# US_SB_USB.net
KiCad netlist of a schematic drawn in Altium Designer
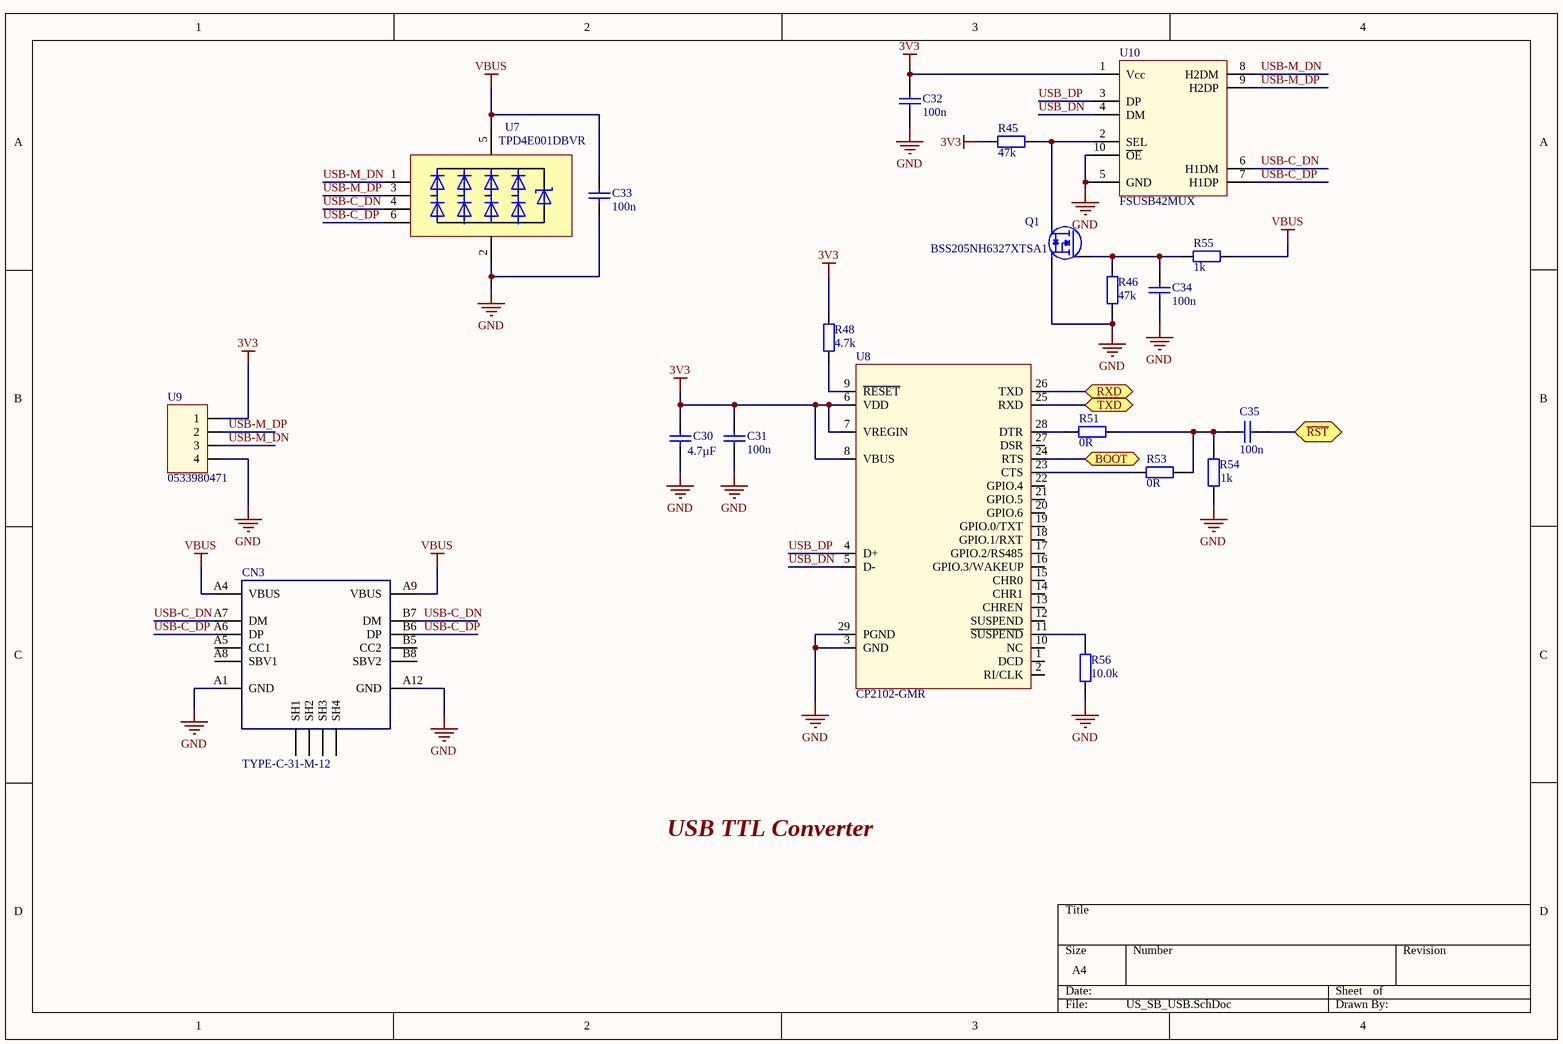
[diagram p0: US_SB_USB.SchDoc]

(export (version "E")
  (design (tool "Eeschema 10.0.6"))
  (components
    (comp (ref "C30")
      (value "4.7µF")
      (footprint "C0603_IPC_HD")
      (description "4.7µF ±10% 10V Ceramic Capacitor X5R 0603 (1608 Metric)")
      (fields
        (field (name "MANUFACTURER") "Samsung Electro-Mechanics")
        (field (name "MANUFACTURER PART NUMBER") "CL10A475KP8NNNC")
      )
      (libsource (lib "alfasat_lib_eps") (part "CL0603_4.7uF_10V"))
    )
    (comp (ref "C31")
      (value "100n")
      (footprint "C0603_IPC_HD")
      (description "CAP CER 0.1UF 16V X7R 0603")
      (fields
        (field (name "MANUFACTURER") "Samsung Electro-Mechanics")
        (field (name "MANUFACTURER PART NUMBER") "CL10B104KO8NNNC")
      )
      (libsource (lib "alfasat_parts_lib") (part "CL10B104KO8NNNC"))
    )
    (comp (ref "C32")
      (value "100n")
      (footprint "C0603_IPC_HD")
      (description "CAP CER 0.1UF 16V X7R 0603")
      (fields
        (field (name "MANUFACTURER") "Samsung Electro-Mechanics")
        (field (name "MANUFACTURER PART NUMBER") "CL10B104KO8NNNC")
      )
      (libsource (lib "alfasat_parts_lib") (part "CL10B104KO8NNNC"))
    )
    (comp (ref "C33")
      (value "100n")
      (footprint "C0603_IPC_HD")
      (description "CAP CER 0.1UF 16V X7R 0603")
      (fields
        (field (name "MANUFACTURER") "Samsung Electro-Mechanics")
        (field (name "MANUFACTURER PART NUMBER") "CL10B104KO8NNNC")
      )
      (libsource (lib "alfasat_parts_lib") (part "CL10B104KO8NNNC"))
    )
    (comp (ref "C34")
      (value "100n")
      (footprint "C0603_IPC_HD")
      (description "CAP CER 0.1UF 16V X7R 0603")
      (fields
        (field (name "MANUFACTURER") "Samsung Electro-Mechanics")
        (field (name "MANUFACTURER PART NUMBER") "CL10B104KO8NNNC")
      )
      (libsource (lib "alfasat_parts_lib") (part "CL10B104KO8NNNC"))
    )
    (comp (ref "C35")
      (value "100n")
      (footprint "C0603_IPC_HD")
      (description "CAP CER 0.1UF 16V X7R 0603")
      (fields
        (field (name "MANUFACTURER") "Samsung Electro-Mechanics")
        (field (name "MANUFACTURER PART NUMBER") "CL10B104KO8NNNC")
      )
      (libsource (lib "alfasat_parts_lib") (part "CL10B104KO8NNNC"))
    )
    (comp (ref "CN3")
      (value "TYPE-C-31-M-12")
      (footprint "TYPE-C-C165948")
      (description "TYPE C PCB TH CONN")
      (fields (field (name "MANUFACTURER") "Korean Hroparts Elec"))
      (libsource (lib "alfasat_lib") (part "TYPE-C-31-M-12"))
    )
    (comp (ref "Q1")
      (value "BSS205NH6327XTSA1")
      (description "N-Channel 20V 2.5A (Ta) 500mW (Ta) Surface Mount SOT-23-3")
      (fields (field (name "MANUFACTURER") "Infineon Technologies"))
      (libsource (lib "alfasat_lib_eps") (part "BSS205NH6327XTSA1"))
    )
    (comp (ref "R45")
      (value "47k")
      (footprint "R0603_IPC_HD")
      (description "RES SMD 47K OHM 5% 1/10W 0603")
      (fields
        (field (name "MANUFACTURER") "Bourns Inc.")
        (field (name "MANUFACTURER PART NUMBER") "CR0603-JW-473ELF")
      )
      (libsource (lib "") (part "CR0603-JW-473ELF_1"))
    )
    (comp (ref "R46")
      (value "47k")
      (footprint "R0603_IPC_HD")
      (description "RES SMD 47K OHM 5% 1/10W 0603")
      (fields
        (field (name "MANUFACTURER") "Bourns Inc.")
        (field (name "MANUFACTURER PART NUMBER") "CR0603-JW-473ELF")
      )
      (libsource (lib "alfasat_lib_eps") (part "CR0603-JW-473ELF"))
    )
    (comp (ref "R48")
      (value "4.7k")
      (footprint "R0603_IPC_HD")
      (description "RES SMD 4.7K OHM 5% 1/10W 0603")
      (fields
        (field (name "MANUFACTURER") "Bourns Inc.")
        (field (name "MANUFACTURER PART NUMBER") "CR0603-JW-472ELF")
      )
      (libsource (lib "alfasat_lib_eps") (part "CR0603-JW-4.7k"))
    )
    (comp (ref "R51")
      (value "0R")
      (footprint "R0603_IPC_MD")
      (description "RES SMD 0 OHM JUMPER 1/10W 0603")
      (fields
        (field (name "MANUFACTURER") "Bourns Inc.")
        (field (name "MANUFACTURER PART NUMBER") "CR0603-J/-000ELF")
      )
      (libsource (lib "alfasat_lib") (part "CR0603-J/-000ELF"))
    )
    (comp (ref "R53")
      (value "0R")
      (footprint "R0603_IPC_MD")
      (description "RES SMD 0 OHM JUMPER 1/10W 0603")
      (fields
        (field (name "MANUFACTURER") "Bourns Inc.")
        (field (name "MANUFACTURER PART NUMBER") "CR0603-J/-000ELF")
      )
      (libsource (lib "alfasat_lib") (part "CR0603-J/-000ELF"))
    )
    (comp (ref "R54")
      (value "1k")
      (footprint "R0603_IPC_MD")
      (description "RES SMD 1K OHM 5% 1/10W 0603")
      (fields
        (field (name "MANUFACTURER") "Bourns Inc.")
        (field (name "MANUFACTURER PART NUMBER") "CR0603-JW-102ELF")
      )
      (libsource (lib "alfasat_lib") (part "CR0603-JW-102ELF"))
    )
    (comp (ref "R55")
      (value "1k")
      (footprint "R0603_IPC_MD")
      (description "RES SMD 1K OHM 5% 1/10W 0603")
      (fields
        (field (name "MANUFACTURER") "Bourns Inc.")
        (field (name "MANUFACTURER PART NUMBER") "CR0603-JW-102ELF")
      )
      (libsource (lib "") (part "CR0603-JW-102ELF_1"))
    )
    (comp (ref "R56")
      (value "10.0k")
      (footprint "R0603_IPC_MD")
      (description "RES 10K OHM 1% 1/10W 0603")
      (fields
        (field (name "MANUFACTURER") "Stackpole Electronics Inc")
        (field (name "MANUFACTURER PART NUMBER") "RMCF0603FT10K0")
      )
      (libsource (lib "alfasat_parts_lib") (part "RMCF0603FT10K0"))
    )
    (comp (ref "U7")
      (value "TPD4E001DBVR")
      (footprint "SOT23-6")
      (description "4x TVS DIODE 5.5V SOT23-6")
      (fields (field (name "MANUFACTURER") "TI"))
      (libsource (lib "alfasat_parts_lib") (part "TPD4E001DBVR"))
    )
    (comp (ref "U8")
      (value "CP2102-GMR")
      (footprint "CP2102\\9_QFN50P500X500X80_HS-29N")
      (description "USB Bridge, USB to UART USB 2.0 UART Interface 28-QFN (5x5)")
      (fields
        (field (name "MANUFACTURER") "Silicon Labs")
        (field (name "MANUFACTURER PART NUMBER") "CP2102N-A01-GQFN28R")
      )
      (libsource (lib "alfasat_lib_eps") (part "CP2102N-A01-GQFN28R"))
    )
    (comp (ref "U9")
      (value "0533980471")
      (footprint "PB_53261-0471_Right")
      (description "Connector Header Surface Mount 4 position 0.049\" (1.25mm)")
      (fields (field (name "MANUFACTURER") "Molex"))
      (libsource (lib "alfasat_lib_eps") (part "PB_053398_0471"))
    )
    (comp (ref "U10")
      (value "FSUSB42MUX")
      (footprint "MSOP-10")
      (description "IC USB SWITCH DPDT 10MSOP")
      (fields (field (name "MANUFACTURER") "ON Semiconductor"))
      (libsource (lib "alfasat_lib") (part "FSUSB42MUX"))
    )
  )
  (nets
    (net (code "1") (name "/BOOT") (class "Default")
      (node (ref "U8") (pin "24") (pinfunction "RTS_24") (pintype "passive"))
    )
    (net (code "2") (name "/RXD") (class "Default")
      (node (ref "U8") (pin "26") (pinfunction "TXD_26") (pintype "passive"))
    )
    (net (code "3") (name "/TXD") (class "Default")
      (node (ref "U8") (pin "25") (pinfunction "RXD_25") (pintype "passive"))
    )
    (net (code "4") (name "/USB-C_DN") (class "Default")
      (node (ref "CN3") (pin "A7") (pinfunction "DM_A7") (pintype "passive"))
      (node (ref "CN3") (pin "B7") (pinfunction "DM_B7") (pintype "passive"))
      (node (ref "U10") (pin "6") (pinfunction "H1DM_6") (pintype "passive"))
      (node (ref "U7") (pin "4") (pinfunction "IO3_4") (pintype "passive"))
    )
    (net (code "5") (name "/USB-C_DP") (class "Default")
      (node (ref "CN3") (pin "A6") (pinfunction "DP_A6") (pintype "passive"))
      (node (ref "CN3") (pin "B6") (pinfunction "DP_B6") (pintype "passive"))
      (node (ref "U10") (pin "7") (pinfunction "H1DP_7") (pintype "passive"))
      (node (ref "U7") (pin "6") (pinfunction "IO4_6") (pintype "passive"))
    )
    (net (code "6") (name "/USB-M_DN") (class "Default")
      (node (ref "U10") (pin "8") (pinfunction "H2DM_8") (pintype "passive"))
      (node (ref "U7") (pin "1") (pinfunction "IO1_1") (pintype "passive"))
      (node (ref "U9") (pin "3") (pinfunction "3_3") (pintype "passive"))
    )
    (net (code "7") (name "/USB-M_DP") (class "Default")
      (node (ref "U10") (pin "9") (pinfunction "H2DP_9") (pintype "passive"))
      (node (ref "U7") (pin "3") (pinfunction "IO2_3") (pintype "passive"))
      (node (ref "U9") (pin "2") (pinfunction "2_2") (pintype "passive"))
    )
    (net (code "8") (name "/USB_DN") (class "Default")
      (node (ref "U10") (pin "4") (pinfunction "DM_4") (pintype "passive"))
      (node (ref "U8") (pin "5") (pinfunction "D-_5") (pintype "passive"))
    )
    (net (code "9") (name "/USB_DP") (class "Default")
      (node (ref "U10") (pin "3") (pinfunction "DP_3") (pintype "passive"))
      (node (ref "U8") (pin "4") (pinfunction "D+_4") (pintype "passive"))
    )
    (net (code "10") (name "/~{RST}") (class "Default")
      (node (ref "C35") (pin "1") (pinfunction "1_1") (pintype "passive"))
    )
    (net (code "11") (name "3V3") (class "Default")
      (node (ref "C30") (pin "2") (pinfunction "2_2") (pintype "passive"))
      (node (ref "C31") (pin "2") (pinfunction "2_2") (pintype "passive"))
      (node (ref "C32") (pin "2") (pinfunction "2_2") (pintype "passive"))
      (node (ref "R45") (pin "2") (pinfunction "2_2") (pintype "passive"))
      (node (ref "R48") (pin "2") (pinfunction "2_2") (pintype "passive"))
      (node (ref "U10") (pin "1") (pinfunction "Vcc_1") (pintype "passive"))
      (node (ref "U8") (pin "6") (pinfunction "VDD_6") (pintype "passive"))
      (node (ref "U8") (pin "7") (pinfunction "VREGIN_7") (pintype "passive"))
      (node (ref "U8") (pin "8") (pinfunction "VBUS_8") (pintype "passive"))
      (node (ref "U9") (pin "1") (pinfunction "1_1") (pintype "passive"))
    )
    (net (code "12") (name "GND") (class "Default")
      (node (ref "C30") (pin "1") (pinfunction "1_1") (pintype "passive"))
      (node (ref "C31") (pin "1") (pinfunction "1_1") (pintype "passive"))
      (node (ref "C32") (pin "1") (pinfunction "1_1") (pintype "passive"))
      (node (ref "C33") (pin "1") (pinfunction "1_1") (pintype "passive"))
      (node (ref "C34") (pin "1") (pinfunction "1_1") (pintype "passive"))
      (node (ref "CN3") (pin "A1") (pinfunction "GND_A1") (pintype "passive"))
      (node (ref "CN3") (pin "A12") (pinfunction "GND_A12") (pintype "passive"))
      (node (ref "Q1") (pin "2") (pinfunction "S_2") (pintype "passive"))
      (node (ref "R46") (pin "2") (pinfunction "2_2") (pintype "passive"))
      (node (ref "R54") (pin "1") (pinfunction "1_1") (pintype "passive"))
      (node (ref "R56") (pin "1") (pinfunction "1_1") (pintype "passive"))
      (node (ref "U10") (pin "10") (pinfunction "~{OE}_10") (pintype "passive"))
      (node (ref "U10") (pin "5") (pinfunction "GND_5") (pintype "passive"))
      (node (ref "U7") (pin "2") (pinfunction "GND_2") (pintype "power_in"))
      (node (ref "U8") (pin "29") (pinfunction "PGND_29") (pintype "passive"))
      (node (ref "U8") (pin "3") (pinfunction "GND_3") (pintype "passive"))
      (node (ref "U9") (pin "4") (pinfunction "4_4") (pintype "passive"))
    )
    (net (code "13") (name "Net-(C35-Pad2)") (class "Default")
      (node (ref "C35") (pin "2") (pinfunction "2_2") (pintype "passive"))
      (node (ref "R51") (pin "1") (pinfunction "1_1") (pintype "passive"))
      (node (ref "R53") (pin "1") (pinfunction "1_1") (pintype "passive"))
      (node (ref "R54") (pin "2") (pinfunction "2_2") (pintype "passive"))
    )
    (net (code "14") (name "Net-(Q1-D)") (class "Default")
      (node (ref "Q1") (pin "3") (pinfunction "D_3") (pintype "passive"))
      (node (ref "R45") (pin "1") (pinfunction "1_1") (pintype "passive"))
      (node (ref "U10") (pin "2") (pinfunction "SEL_2") (pintype "passive"))
    )
    (net (code "15") (name "Net-(Q1-G)") (class "Default")
      (node (ref "C34") (pin "2") (pinfunction "2_2") (pintype "passive"))
      (node (ref "Q1") (pin "1") (pinfunction "G_1") (pintype "passive"))
      (node (ref "R46") (pin "1") (pinfunction "1_1") (pintype "passive"))
      (node (ref "R55") (pin "2") (pinfunction "2_2") (pintype "passive"))
    )
    (net (code "16") (name "Net-(U8-CTS)") (class "Default")
      (node (ref "R53") (pin "2") (pinfunction "2_2") (pintype "passive"))
      (node (ref "U8") (pin "23") (pinfunction "CTS_23") (pintype "passive"))
    )
    (net (code "17") (name "Net-(U8-DTR)") (class "Default")
      (node (ref "R51") (pin "2") (pinfunction "2_2") (pintype "passive"))
      (node (ref "U8") (pin "28") (pinfunction "DTR_28") (pintype "passive"))
    )
    (net (code "18") (name "Net-(U8-~{RESET})") (class "Default")
      (node (ref "R48") (pin "1") (pinfunction "1_1") (pintype "passive"))
      (node (ref "U8") (pin "9") (pinfunction "~{RESET}_9") (pintype "passive"))
    )
    (net (code "19") (name "Net-(U8-~{SUSPEND})") (class "Default")
      (node (ref "R56") (pin "2") (pinfunction "2_2") (pintype "passive"))
      (node (ref "U8") (pin "11") (pinfunction "~{SUSPEND}_11") (pintype "passive"))
    )
    (net (code "20") (name "VBUS") (class "Default")
      (node (ref "C33") (pin "2") (pinfunction "2_2") (pintype "passive"))
      (node (ref "CN3") (pin "A4") (pinfunction "VBUS_A4") (pintype "passive"))
      (node (ref "CN3") (pin "A9") (pinfunction "VBUS_A9") (pintype "passive"))
      (node (ref "R55") (pin "1") (pinfunction "1_1") (pintype "passive"))
      (node (ref "U7") (pin "5") (pinfunction "VCC_5") (pintype "power_in"))
    )
    (net (code "21") (name "unconnected-(CN3-CC1-PadA5)") (class "Default")
      (node (ref "CN3") (pin "A5") (pinfunction "CC1_A5") (pintype "passive"))
    )
    (net (code "22") (name "unconnected-(CN3-CC2-PadB5)") (class "Default")
      (node (ref "CN3") (pin "B5") (pinfunction "CC2_B5") (pintype "passive"))
    )
    (net (code "23") (name "unconnected-(CN3-PadSH1)") (class "Default")
      (node (ref "CN3") (pin "SH1") (pinfunction "SH1_SH1") (pintype "passive"))
    )
    (net (code "24") (name "unconnected-(CN3-PadSH2)") (class "Default")
      (node (ref "CN3") (pin "SH2") (pinfunction "SH2_SH2") (pintype "passive"))
    )
    (net (code "25") (name "unconnected-(CN3-PadSH3)") (class "Default")
      (node (ref "CN3") (pin "SH3") (pinfunction "SH3_SH3") (pintype "passive"))
    )
    (net (code "26") (name "unconnected-(CN3-PadSH4)") (class "Default")
      (node (ref "CN3") (pin "SH4") (pinfunction "SH4_SH4") (pintype "passive"))
    )
    (net (code "27") (name "unconnected-(CN3-SBV1-PadA8)") (class "Default")
      (node (ref "CN3") (pin "A8") (pinfunction "SBV1_A8") (pintype "passive"))
    )
    (net (code "28") (name "unconnected-(CN3-SBV2-PadB8)") (class "Default")
      (node (ref "CN3") (pin "B8") (pinfunction "SBV2_B8") (pintype "passive"))
    )
    (net (code "29") (name "unconnected-(U8-CHR0-Pad15)") (class "Default")
      (node (ref "U8") (pin "15") (pinfunction "CHR0_15") (pintype "passive"))
    )
    (net (code "30") (name "unconnected-(U8-CHR1-Pad14)") (class "Default")
      (node (ref "U8") (pin "14") (pinfunction "CHR1_14") (pintype "passive"))
    )
    (net (code "31") (name "unconnected-(U8-CHREN-Pad13)") (class "Default")
      (node (ref "U8") (pin "13") (pinfunction "CHREN_13") (pintype "passive"))
    )
    (net (code "32") (name "unconnected-(U8-DCD-Pad1)") (class "Default")
      (node (ref "U8") (pin "1") (pinfunction "DCD_1") (pintype "passive"))
    )
    (net (code "33") (name "unconnected-(U8-DSR-Pad27)") (class "Default")
      (node (ref "U8") (pin "27") (pinfunction "DSR_27") (pintype "passive"))
    )
    (net (code "34") (name "unconnected-(U8-GPIO.0{slash}TXT-Pad19)") (class "Default")
      (node (ref "U8") (pin "19") (pinfunction "GPIO.0/TXT_19") (pintype "passive"))
    )
    (net (code "35") (name "unconnected-(U8-GPIO.1{slash}RXT-Pad18)") (class "Default")
      (node (ref "U8") (pin "18") (pinfunction "GPIO.1/RXT_18") (pintype "passive"))
    )
    (net (code "36") (name "unconnected-(U8-GPIO.2{slash}RS485-Pad17)") (class "Default")
      (node (ref "U8") (pin "17") (pinfunction "GPIO.2/RS485_17") (pintype "passive"))
    )
    (net (code "37") (name "unconnected-(U8-GPIO.3{slash}WAKEUP-Pad16)") (class "Default")
      (node (ref "U8") (pin "16") (pinfunction "GPIO.3/WAKEUP_16") (pintype "passive"))
    )
    (net (code "38") (name "unconnected-(U8-GPIO.4-Pad22)") (class "Default")
      (node (ref "U8") (pin "22") (pinfunction "GPIO.4_22") (pintype "passive"))
    )
    (net (code "39") (name "unconnected-(U8-GPIO.5-Pad21)") (class "Default")
      (node (ref "U8") (pin "21") (pinfunction "GPIO.5_21") (pintype "passive"))
    )
    (net (code "40") (name "unconnected-(U8-GPIO.6-Pad20)") (class "Default")
      (node (ref "U8") (pin "20") (pinfunction "GPIO.6_20") (pintype "passive"))
    )
    (net (code "41") (name "unconnected-(U8-NC-Pad10)") (class "Default")
      (node (ref "U8") (pin "10") (pinfunction "NC_10") (pintype "passive"))
    )
    (net (code "42") (name "unconnected-(U8-RI{slash}CLK-Pad2)") (class "Default")
      (node (ref "U8") (pin "2") (pinfunction "RI/CLK_2") (pintype "passive"))
    )
    (net (code "43") (name "unconnected-(U8-SUSPEND-Pad12)") (class "Default")
      (node (ref "U8") (pin "12") (pinfunction "SUSPEND_12") (pintype "passive"))
    )
  )
)
